# Ham-Dip-V2-004-A.net
KiCad netlist of a schematic drawn in EAGLE
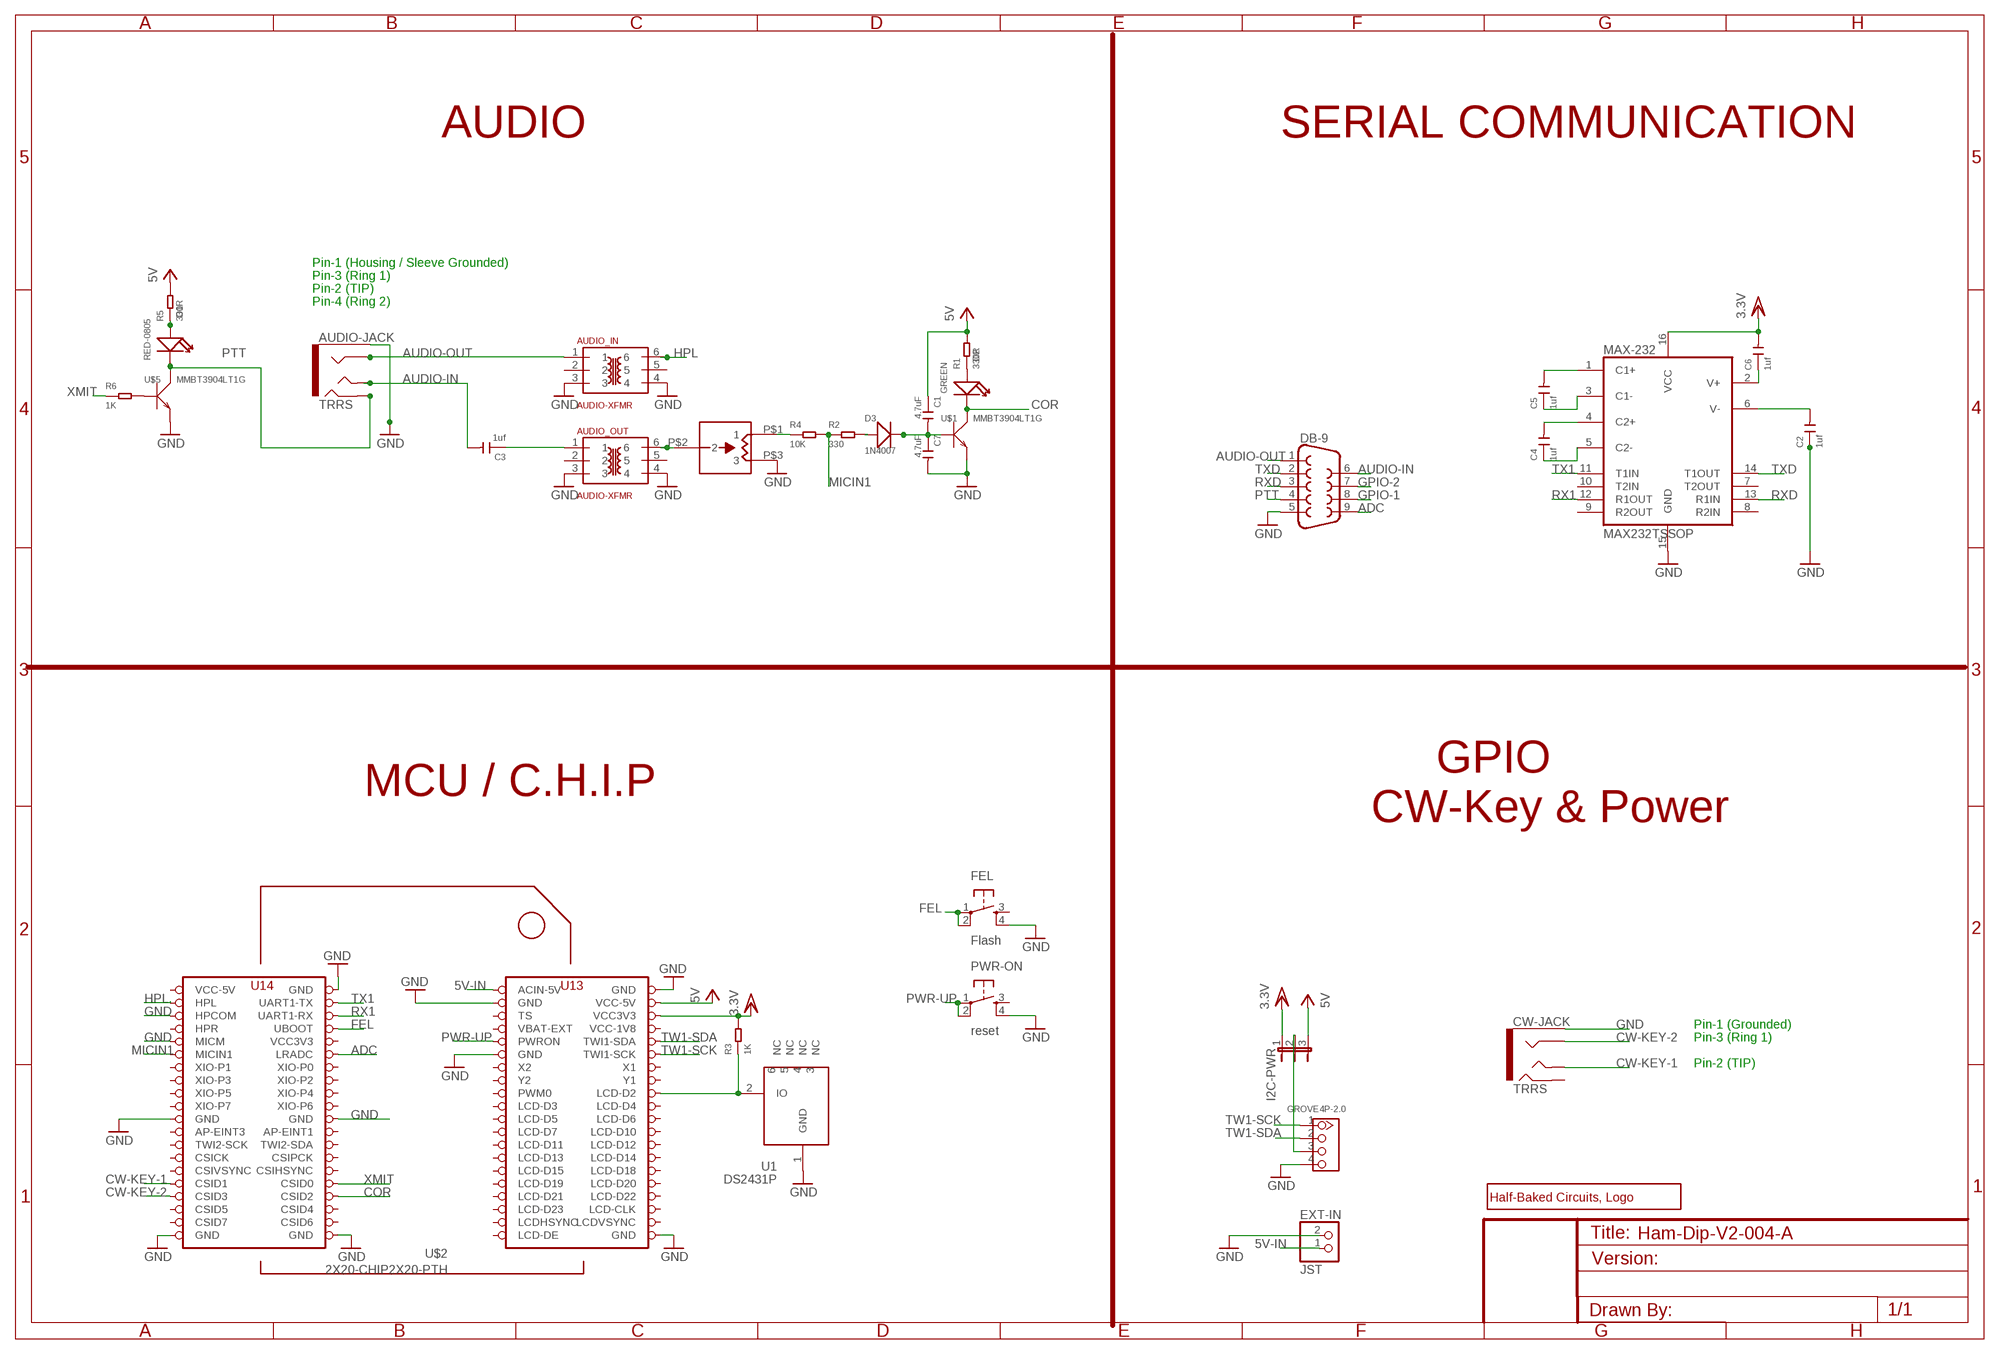
[diagram p0: schematic, sheet 1]

(export (version "E")
  (design (tool "Eeschema 10.0.6"))
  (components
    (comp (ref "AUDIO-JACK")
      (value "TRRS")
      (footprint "eagle-import:AUDIO-JACK-TRRS-SMD")
      (libsource (lib "eagle-import") (part "AUDIO-JACK3"))
    )
    (comp (ref "AUDIO_IN")
      (value "AUDIO-XFMR")
      (footprint "eagle-import:SM-LP-5001")
      (libsource (lib "eagle-import") (part "SM-LP-5001"))
    )
    (comp (ref "AUDIO_OUT")
      (value "AUDIO-XFMR")
      (footprint "eagle-import:SM-LP-5001")
      (libsource (lib "eagle-import") (part "SM-LP-5001"))
    )
    (comp (ref "C1")
      (value "4.7uF")
      (footprint "eagle-import:C0805")
      (fields (field (name "MPN") "CC0805KKX7R8BB105"))
      (libsource (lib "eagle-import") (part "CERAMIC-1UF-25V-10%-X7R(0805)"))
    )
    (comp (ref "C2")
      (value "1uf")
      (footprint "eagle-import:C0805")
      (fields (field (name "MPN") "CC0805KKX7R8BB105"))
      (libsource (lib "eagle-import") (part "CERAMIC-1UF-25V-10%-X7R(0805)"))
    )
    (comp (ref "C3")
      (value "1uf")
      (footprint "eagle-import:C0805")
      (fields (field (name "MPN") "CC0805KKX7R8BB105"))
      (libsource (lib "eagle-import") (part "CERAMIC-1UF-25V-10%-X7R(0805)"))
    )
    (comp (ref "C4")
      (value "1uf")
      (footprint "eagle-import:C0805")
      (fields (field (name "MPN") "CC0805KKX7R8BB105"))
      (libsource (lib "eagle-import") (part "CERAMIC-1UF-25V-10%-X7R(0805)"))
    )
    (comp (ref "C5")
      (value "1uf")
      (footprint "eagle-import:C0805")
      (fields (field (name "MPN") "CC0805KKX7R8BB105"))
      (libsource (lib "eagle-import") (part "CERAMIC-1UF-25V-10%-X7R(0805)"))
    )
    (comp (ref "C6")
      (value "1uf")
      (footprint "eagle-import:C0805")
      (fields (field (name "MPN") "CC0805KKX7R8BB105"))
      (libsource (lib "eagle-import") (part "CERAMIC-1UF-25V-10%-X7R(0805)"))
    )
    (comp (ref "C7")
      (value "4.7uF")
      (footprint "eagle-import:C0805")
      (fields (field (name "MPN") "CC0805KKX7R8BB105"))
      (libsource (lib "eagle-import") (part "CERAMIC-1UF-25V-10%-X7R(0805)"))
    )
    (comp (ref "CW-JACK")
      (value "TRRS")
      (footprint "eagle-import:AUDIO-JACK-TRRS-SMD")
      (libsource (lib "eagle-import") (part "AUDIO-JACK3"))
    )
    (comp (ref "D1")
      (value "RED-0805")
      (footprint "eagle-import:LED-0805")
      (fields (field (name "MPN") "17-215SURC/S530-A2/TR8"))
      (libsource (lib "eagle-import") (part "SMD-LED-CLEAR-RED(0805)"))
    )
    (comp (ref "D2")
      (value "GREEN")
      (footprint "eagle-import:LED-0805")
      (fields (field (name "MPN") "17-215SURC/S530-A2/TR8"))
      (libsource (lib "eagle-import") (part "SMD-LED-CLEAR-RED(0805)"))
    )
    (comp (ref "D3")
      (value "1N4007")
      (footprint "eagle-import:DO-214AC")
      (libsource (lib "eagle-import") (part "DIODE-GEN-PURPOSE-1KV-1A(DO-214AC)"))
    )
    (comp (ref "DB-9")
      (value "DB9FEMALE")
      (footprint "eagle-import:DB9")
      (libsource (lib "eagle-import") (part "DB9FEMALE"))
    )
    (comp (ref "EXT-IN")
      (value "JST")
      (footprint "eagle-import:JST-PH-2-THM")
      (libsource (lib "eagle-import") (part "JST_2PIN-THM"))
    )
    (comp (ref "FEL")
      (value "Flash")
      (footprint "eagle-import:TACTILE_SWITCH_SMD")
      (libsource (lib "eagle-import") (part "TAC_SWITCHSMD"))
    )
    (comp (ref "GROVE")
      (value "4P-2.0")
      (footprint "eagle-import:HW4-2.0")
      (libsource (lib "eagle-import") (part "GROVE-CONNECTOR-DIP(4P-2.0)"))
    )
    (comp (ref "I2C-PWR")
      (value "JP2E")
      (footprint "eagle-import:JP2")
      (libsource (lib "eagle-import") (part "JP2E"))
    )
    (comp (ref "MAX-232")
      (value "MAX232TSSOP")
      (footprint "eagle-import:TSSOP16")
      (libsource (lib "eagle-import") (part "MAX232TSSOP"))
    )
    (comp (ref "MIC-LVL")
      (value "1K")
      (footprint "eagle-import:TC33X")
      (libsource (lib "eagle-import") (part "TC33X"))
    )
    (comp (ref "PWR-ON")
      (value "reset")
      (footprint "eagle-import:TACTILE_SWITCH_SMD")
      (libsource (lib "eagle-import") (part "TAC_SWITCHSMD"))
    )
    (comp (ref "R1")
      (value "330R")
      (footprint "eagle-import:R0805")
      (fields (field (name "MPN") "RC0805JR-07220RL"))
      (libsource (lib "eagle-import") (part "SMD-RES-220R-5%-1/8W(0805)"))
    )
    (comp (ref "R2")
      (value "330")
      (footprint "eagle-import:R0805")
      (fields (field (name "MPN") "RC0805JR-07220RL"))
      (libsource (lib "eagle-import") (part "SMD-RES-220R-5%-1/8W(0805)"))
    )
    (comp (ref "R3")
      (value "1K")
      (footprint "eagle-import:R0805")
      (fields (field (name "MPN") "RC0805JR-07220RL"))
      (libsource (lib "eagle-import") (part "SMD-RES-220R-5%-1/8W(0805)"))
    )
    (comp (ref "R4")
      (value "10K")
      (footprint "eagle-import:R0805")
      (fields (field (name "MPN") "RC0805FR-0710KL"))
      (libsource (lib "eagle-import") (part "SMD-RES-10K-1%-1/8W(0805)"))
    )
    (comp (ref "R5")
      (value "330R")
      (footprint "eagle-import:R0805")
      (fields (field (name "MPN") "RC0805JR-07220RL"))
      (libsource (lib "eagle-import") (part "SMD-RES-220R-5%-1/8W(0805)"))
    )
    (comp (ref "R6")
      (value "1K")
      (footprint "eagle-import:R0805")
      (fields (field (name "MPN") "RC0805JR-07220RL"))
      (libsource (lib "eagle-import") (part "SMD-RES-220R-5%-1/8W(0805)"))
    )
    (comp (ref "U$1")
      (value "MMBT3904LT1G")
      (footprint "eagle-import:SOT-23")
      (libsource (lib "eagle-import") (part "SMD-TRANSISTORS-NPN-40V-200MA-MMBT3904LT1G(SOT-23)"))
    )
    (comp (ref "U$2")
      (value "2X20-CHIP2X20-PTH")
      (footprint "eagle-import:2X20CHIP-TH")
      (fields (field (name "VENDOR_PART_NUMBER") "AWHW40-G-SMD-R (single)"))
      (libsource (lib "eagle-import") (part "2X20-CHIP2X20-PTH-CHIP_A"))
    )
    (comp (ref "U$4")
      (value "HAM-DIP")
      (footprint "eagle-import:HAM-DIP")
      (libsource (lib "eagle-import") (part "HAM-DIP"))
    )
    (comp (ref "U$5")
      (value "MMBT3904LT1G")
      (footprint "eagle-import:SOT-23")
      (libsource (lib "eagle-import") (part "SMD-TRANSISTORS-NPN-40V-200MA-MMBT3904LT1G(SOT-23)"))
    )
    (comp (ref "U1")
      (value "DS2431P")
      (footprint "eagle-import:TSOC6")
      (fields (field (name "MFG") "DIGIKEY") (field (name "VENDOR_PART_NUMBER") "DS2431P+T&R"))
      (libsource (lib "eagle-import") (part "DS2431P"))
    )
  )
  (nets
    (net (code "1") (name "/5V-IN") (class "Default")
      (node (ref "EXT-IN") (pin "1") (pinfunction "2_1") (pintype "passive"))
      (node (ref "U$2") (pin "CHG-IN") (pinfunction "ACIN-5V_CHG-IN") (pintype "passive"))
    )
    (net (code "2") (name "/ADC") (class "Default")
      (node (ref "DB-9") (pin "9") (pinfunction "9_9") (pintype "passive"))
      (node (ref "U$2") (pin "LRADC") (pinfunction "LRADC_LRADC") (pintype "passive"))
    )
    (net (code "3") (name "/AUDIO-IN") (class "Default")
      (node (ref "AUDIO-JACK") (pin "TIP") (pinfunction "TIP_TIP") (pintype "bidirectional"))
      (node (ref "C3") (pin "2") (pinfunction "2_2") (pintype "passive"))
      (node (ref "DB-9") (pin "6") (pinfunction "6_6") (pintype "passive"))
    )
    (net (code "4") (name "/AUDIO-OUT") (class "Default")
      (node (ref "AUDIO-JACK") (pin "RING1") (pinfunction "RING1_RING1") (pintype "bidirectional"))
      (node (ref "AUDIO_IN") (pin "1") (pinfunction "1_1") (pintype "bidirectional"))
      (node (ref "DB-9") (pin "1") (pinfunction "1_1") (pintype "passive"))
    )
    (net (code "5") (name "/COR") (class "Default")
      (node (ref "D2") (pin "-") (pinfunction "-_-") (pintype "passive"))
      (node (ref "U$1") (pin "3") (pinfunction "C_3") (pintype "passive"))
      (node (ref "U$2") (pin "CSID2") (pinfunction "CSID2_CSID2") (pintype "passive"))
    )
    (net (code "6") (name "/CW-KEY-1") (class "Default")
      (node (ref "CW-JACK") (pin "TIP") (pinfunction "TIP_TIP") (pintype "bidirectional"))
      (node (ref "U$2") (pin "CSID1") (pinfunction "CSID1_CSID1") (pintype "passive"))
    )
    (net (code "7") (name "/CW-KEY-2") (class "Default")
      (node (ref "CW-JACK") (pin "RING1") (pinfunction "RING1_RING1") (pintype "bidirectional"))
      (node (ref "U$2") (pin "CSID3") (pinfunction "CSID3_CSID3") (pintype "passive"))
    )
    (net (code "8") (name "/FEL") (class "Default")
      (node (ref "FEL") (pin "1") (pinfunction "1_1") (pintype "passive"))
      (node (ref "FEL") (pin "2") (pinfunction "2_2") (pintype "passive"))
      (node (ref "U$2") (pin "FEL") (pinfunction "UBOOT_FEL") (pintype "passive"))
    )
    (net (code "9") (name "/GPIO-1") (class "Default")
      (node (ref "DB-9") (pin "8") (pinfunction "8_8") (pintype "passive"))
    )
    (net (code "10") (name "/GPIO-2") (class "Default")
      (node (ref "DB-9") (pin "7") (pinfunction "7_7") (pintype "passive"))
    )
    (net (code "11") (name "/HPL") (class "Default")
      (node (ref "AUDIO_IN") (pin "6") (pinfunction "6_6") (pintype "bidirectional"))
      (node (ref "U$2") (pin "HPL") (pinfunction "HPL_HPL") (pintype "passive"))
    )
    (net (code "12") (name "/MICIN1") (class "Default")
      (node (ref "R2") (pin "1") (pinfunction "1_1") (pintype "passive"))
      (node (ref "R4") (pin "2") (pinfunction "2_2") (pintype "passive"))
      (node (ref "U$2") (pin "MICIN1") (pinfunction "MICIN1_MICIN1") (pintype "passive"))
    )
    (net (code "13") (name "/PTT") (class "Default")
      (node (ref "AUDIO-JACK") (pin "RING2") (pinfunction "RING2_RING2") (pintype "bidirectional"))
      (node (ref "D1") (pin "-") (pinfunction "-_-") (pintype "passive"))
      (node (ref "DB-9") (pin "4") (pinfunction "4_4") (pintype "passive"))
      (node (ref "U$5") (pin "3") (pinfunction "C_3") (pintype "passive"))
    )
    (net (code "14") (name "/PWR-UP") (class "Default")
      (node (ref "PWR-ON") (pin "1") (pinfunction "1_1") (pintype "passive"))
      (node (ref "PWR-ON") (pin "2") (pinfunction "2_2") (pintype "passive"))
      (node (ref "U$2") (pin "PWRON") (pinfunction "PWRON_PWRON") (pintype "passive"))
    )
    (net (code "15") (name "/RX1") (class "Default")
      (node (ref "MAX-232") (pin "12") (pinfunction "R1OUT_12") (pintype "output"))
      (node (ref "U$2") (pin "UART1-RX") (pinfunction "UART1-RX_UART1-RX") (pintype "passive"))
    )
    (net (code "16") (name "/RXD") (class "Default")
      (node (ref "DB-9") (pin "3") (pinfunction "3_3") (pintype "passive"))
      (node (ref "MAX-232") (pin "13") (pinfunction "R1IN_13") (pintype "input"))
    )
    (net (code "17") (name "/TW1-SCK") (class "Default")
      (node (ref "GROVE") (pin "1") (pinfunction "1_1") (pintype "bidirectional"))
      (node (ref "U$2") (pin "TWI1-SCK") (pinfunction "TWI1-SCK_TWI1-SCK") (pintype "passive"))
    )
    (net (code "18") (name "/TW1-SDA") (class "Default")
      (node (ref "GROVE") (pin "2") (pinfunction "2_2") (pintype "bidirectional"))
      (node (ref "U$2") (pin "TWI1-SDA") (pinfunction "TWI1-SDA_TWI1-SDA") (pintype "passive"))
    )
    (net (code "19") (name "/TX1") (class "Default")
      (node (ref "MAX-232") (pin "11") (pinfunction "T1IN_11") (pintype "input"))
      (node (ref "U$2") (pin "UART1-TX") (pinfunction "UART1-TX_UART1-TX") (pintype "passive"))
    )
    (net (code "20") (name "/TXD") (class "Default")
      (node (ref "DB-9") (pin "2") (pinfunction "2_2") (pintype "passive"))
      (node (ref "MAX-232") (pin "14") (pinfunction "T1OUT_14") (pintype "output"))
    )
    (net (code "21") (name "/VCC-1V8") (class "Default")
      (node (ref "U$2") (pin "VCC1V8") (pinfunction "VCC-1V8_VCC1V8") (pintype "power_in"))
    )
    (net (code "22") (name "/VCC-5V") (class "Default")
      (node (ref "U$2") (pin "VCC5V@1") (pinfunction "VCC-5V_VCC5V@1") (pintype "power_in"))
    )
    (net (code "23") (name "/VCC3V3") (class "Default")
      (node (ref "U$2") (pin "VCC3V3@1") (pinfunction "VCC3V3_VCC3V3@1") (pintype "power_in"))
    )
    (net (code "24") (name "/XMIT") (class "Default")
      (node (ref "R6") (pin "1") (pinfunction "1_1") (pintype "passive"))
      (node (ref "U$2") (pin "CSID0") (pinfunction "CSID0_CSID0") (pintype "passive"))
    )
    (net (code "25") (name "3.3V") (class "Default")
      (node (ref "C6") (pin "2") (pinfunction "2_2") (pintype "passive"))
      (node (ref "I2C-PWR") (pin "1") (pinfunction "1_1") (pintype "passive"))
      (node (ref "MAX-232") (pin "16") (pinfunction "VCC_16") (pintype "bidirectional"))
      (node (ref "R3") (pin "2") (pinfunction "2_2") (pintype "passive"))
      (node (ref "U$2") (pin "VCC3V3") (pinfunction "VCC3V3_VCC3V3") (pintype "power_in"))
    )
    (net (code "26") (name "5V") (class "Default")
      (node (ref "C1") (pin "1") (pinfunction "1_1") (pintype "passive"))
      (node (ref "I2C-PWR") (pin "3") (pinfunction "3_3") (pintype "passive"))
      (node (ref "R1") (pin "2") (pinfunction "2_2") (pintype "passive"))
      (node (ref "R5") (pin "2") (pinfunction "2_2") (pintype "passive"))
      (node (ref "U$2") (pin "VCC5V@0") (pinfunction "VCC-5V_VCC5V@0") (pintype "power_in"))
    )
    (net (code "27") (name "GND") (class "Default")
      (node (ref "AUDIO-JACK") (pin "EARTH") (pinfunction "EARTH_EARTH") (pintype "bidirectional"))
      (node (ref "AUDIO_IN") (pin "3") (pinfunction "3_3") (pintype "bidirectional"))
      (node (ref "AUDIO_IN") (pin "4") (pinfunction "4_4") (pintype "bidirectional"))
      (node (ref "AUDIO_OUT") (pin "3") (pinfunction "3_3") (pintype "bidirectional"))
      (node (ref "AUDIO_OUT") (pin "4") (pinfunction "4_4") (pintype "bidirectional"))
      (node (ref "C2") (pin "1") (pinfunction "1_1") (pintype "passive"))
      (node (ref "C7") (pin "2") (pinfunction "2_2") (pintype "passive"))
      (node (ref "CW-JACK") (pin "EARTH") (pinfunction "EARTH_EARTH") (pintype "bidirectional"))
      (node (ref "DB-9") (pin "5") (pinfunction "5_5") (pintype "passive"))
      (node (ref "EXT-IN") (pin "2") (pinfunction "1_2") (pintype "passive"))
      (node (ref "FEL") (pin "4") (pinfunction "4_4") (pintype "passive"))
      (node (ref "GROVE") (pin "4") (pinfunction "4_4") (pintype "bidirectional"))
      (node (ref "MAX-232") (pin "15") (pinfunction "GND_15") (pintype "bidirectional"))
      (node (ref "MIC-LVL") (pin "P$3") (pinfunction "3_P$3") (pintype "bidirectional"))
      (node (ref "PWR-ON") (pin "4") (pinfunction "4_4") (pintype "passive"))
      (node (ref "U$1") (pin "2") (pinfunction "E_2") (pintype "passive"))
      (node (ref "U$2") (pin "GND@1") (pinfunction "GND_GND@1") (pintype "power_in"))
      (node (ref "U$2") (pin "GND@10") (pinfunction "GND_GND@10") (pintype "power_in"))
      (node (ref "U$2") (pin "GND@2") (pinfunction "GND_GND@2") (pintype "power_in"))
      (node (ref "U$2") (pin "GND@3") (pinfunction "GND_GND@3") (pintype "power_in"))
      (node (ref "U$2") (pin "GND@4") (pinfunction "GND_GND@4") (pintype "power_in"))
      (node (ref "U$2") (pin "GND@5") (pinfunction "GND_GND@5") (pintype "power_in"))
      (node (ref "U$2") (pin "GND@6") (pinfunction "GND_GND@6") (pintype "power_in"))
      (node (ref "U$2") (pin "GND@7") (pinfunction "GND_GND@7") (pintype "power_in"))
      (node (ref "U$2") (pin "GND@8") (pinfunction "GND_GND@8") (pintype "power_in"))
      (node (ref "U$2") (pin "HPCOM") (pinfunction "HPCOM_HPCOM") (pintype "passive"))
      (node (ref "U$2") (pin "MICM") (pinfunction "MICM_MICM") (pintype "passive"))
      (node (ref "U$5") (pin "2") (pinfunction "E_2") (pintype "passive"))
      (node (ref "U1") (pin "1") (pinfunction "GND_1") (pintype "bidirectional"))
    )
    (net (code "28") (name "Net-(AUDIO_OUT-Pad1)") (class "Default")
      (node (ref "AUDIO_OUT") (pin "1") (pinfunction "1_1") (pintype "bidirectional"))
      (node (ref "C3") (pin "1") (pinfunction "1_1") (pintype "passive"))
    )
    (net (code "29") (name "Net-(D1-Pad+)") (class "Default")
      (node (ref "D1") (pin "+") (pinfunction "+_+") (pintype "passive"))
      (node (ref "R5") (pin "1") (pinfunction "1_1") (pintype "passive"))
    )
    (net (code "30") (name "Net-(D2-Pad+)") (class "Default")
      (node (ref "D2") (pin "+") (pinfunction "+_+") (pintype "passive"))
      (node (ref "R1") (pin "1") (pinfunction "1_1") (pintype "passive"))
    )
    (net (code "31") (name "Net-(D3-+)") (class "Default")
      (node (ref "D3") (pin "1") (pinfunction "+_1") (pintype "passive"))
      (node (ref "R2") (pin "2") (pinfunction "2_2") (pintype "passive"))
    )
    (net (code "32") (name "Net-(D3--)") (class "Default")
      (node (ref "C1") (pin "2") (pinfunction "2_2") (pintype "passive"))
      (node (ref "C7") (pin "1") (pinfunction "1_1") (pintype "passive"))
      (node (ref "D3") (pin "2") (pinfunction "-_2") (pintype "passive"))
      (node (ref "U$1") (pin "1") (pinfunction "B_1") (pintype "passive"))
    )
    (net (code "33") (name "Net-(GROVE-Pad3)") (class "Default")
      (node (ref "GROVE") (pin "3") (pinfunction "3_3") (pintype "bidirectional"))
      (node (ref "I2C-PWR") (pin "2") (pinfunction "2_2") (pintype "passive"))
    )
    (net (code "34") (name "Net-(MAX-232-C1+)") (class "Default")
      (node (ref "C5") (pin "2") (pinfunction "2_2") (pintype "passive"))
      (node (ref "MAX-232") (pin "1") (pinfunction "C1+_1") (pintype "bidirectional"))
    )
    (net (code "35") (name "Net-(MAX-232-C1-)") (class "Default")
      (node (ref "C5") (pin "1") (pinfunction "1_1") (pintype "passive"))
      (node (ref "MAX-232") (pin "3") (pinfunction "C1-_3") (pintype "bidirectional"))
    )
    (net (code "36") (name "Net-(MAX-232-C2+)") (class "Default")
      (node (ref "C4") (pin "2") (pinfunction "2_2") (pintype "passive"))
      (node (ref "MAX-232") (pin "4") (pinfunction "C2+_4") (pintype "bidirectional"))
    )
    (net (code "37") (name "Net-(MAX-232-C2-)") (class "Default")
      (node (ref "C4") (pin "1") (pinfunction "1_1") (pintype "passive"))
      (node (ref "MAX-232") (pin "5") (pinfunction "C2-_5") (pintype "bidirectional"))
    )
    (net (code "38") (name "Net-(MAX-232-V+)") (class "Default")
      (node (ref "C6") (pin "1") (pinfunction "1_1") (pintype "passive"))
      (node (ref "MAX-232") (pin "2") (pinfunction "V+_2") (pintype "bidirectional"))
    )
    (net (code "39") (name "Net-(MAX-232-V-)") (class "Default")
      (node (ref "C2") (pin "2") (pinfunction "2_2") (pintype "passive"))
      (node (ref "MAX-232") (pin "6") (pinfunction "V-_6") (pintype "bidirectional"))
    )
    (net (code "40") (name "Net-(MIC-LVL-1)") (class "Default")
      (node (ref "MIC-LVL") (pin "P$1") (pinfunction "1_P$1") (pintype "bidirectional"))
      (node (ref "R4") (pin "1") (pinfunction "1_1") (pintype "passive"))
    )
    (net (code "41") (name "Net-(MIC-LVL-2)") (class "Default")
      (node (ref "AUDIO_OUT") (pin "6") (pinfunction "6_6") (pintype "bidirectional"))
      (node (ref "MIC-LVL") (pin "P$2") (pinfunction "2_P$2") (pintype "bidirectional"))
    )
    (net (code "42") (name "Net-(U$5-B)") (class "Default")
      (node (ref "R6") (pin "2") (pinfunction "2_2") (pintype "passive"))
      (node (ref "U$5") (pin "1") (pinfunction "B_1") (pintype "passive"))
    )
    (net (code "43") (name "Net-(U1-IO)") (class "Default")
      (node (ref "R3") (pin "1") (pinfunction "1_1") (pintype "passive"))
      (node (ref "U$2") (pin "LCD-D2") (pinfunction "LCD-D2_LCD-D2") (pintype "passive"))
      (node (ref "U1") (pin "2") (pinfunction "IO_2") (pintype "bidirectional"))
    )
    (net (code "44") (name "unconnected-(AUDIO_IN-Pad2)") (class "Default")
      (node (ref "AUDIO_IN") (pin "2") (pinfunction "2_2") (pintype "bidirectional"))
    )
    (net (code "45") (name "unconnected-(AUDIO_IN-Pad5)") (class "Default")
      (node (ref "AUDIO_IN") (pin "5") (pinfunction "5_5") (pintype "bidirectional"))
    )
    (net (code "46") (name "unconnected-(AUDIO_OUT-Pad2)") (class "Default")
      (node (ref "AUDIO_OUT") (pin "2") (pinfunction "2_2") (pintype "bidirectional"))
    )
    (net (code "47") (name "unconnected-(AUDIO_OUT-Pad5)") (class "Default")
      (node (ref "AUDIO_OUT") (pin "5") (pinfunction "5_5") (pintype "bidirectional"))
    )
    (net (code "48") (name "unconnected-(CW-JACK-PadRING2)") (class "Default")
      (node (ref "CW-JACK") (pin "RING2") (pinfunction "RING2_RING2") (pintype "bidirectional"))
    )
    (net (code "49") (name "unconnected-(FEL-Pad3)") (class "Default")
      (node (ref "FEL") (pin "3") (pinfunction "3_3") (pintype "passive"))
    )
    (net (code "50") (name "unconnected-(MAX-232-R2IN-Pad8)") (class "Default")
      (node (ref "MAX-232") (pin "8") (pinfunction "R2IN_8") (pintype "input"))
    )
    (net (code "51") (name "unconnected-(MAX-232-R2OUT-Pad9)") (class "Default")
      (node (ref "MAX-232") (pin "9") (pinfunction "R2OUT_9") (pintype "output"))
    )
    (net (code "52") (name "unconnected-(MAX-232-T2IN-Pad10)") (class "Default")
      (node (ref "MAX-232") (pin "10") (pinfunction "T2IN_10") (pintype "input"))
    )
    (net (code "53") (name "unconnected-(MAX-232-T2OUT-Pad7)") (class "Default")
      (node (ref "MAX-232") (pin "7") (pinfunction "T2OUT_7") (pintype "output"))
    )
    (net (code "54") (name "unconnected-(PWR-ON-Pad3)") (class "Default")
      (node (ref "PWR-ON") (pin "3") (pinfunction "3_3") (pintype "passive"))
    )
    (net (code "55") (name "unconnected-(U$2-LCDHSYNC-PadLCD-HSYNC)") (class "Default")
      (node (ref "U$2") (pin "LCD-HSYNC") (pinfunction "LCDHSYNC_LCD-HSYNC") (pintype "passive"))
    )
    (net (code "56") (name "unconnected-(U$2-LCDVSYNC-PadLCD-VSYNC)") (class "Default")
      (node (ref "U$2") (pin "LCD-VSYNC") (pinfunction "LCDVSYNC_LCD-VSYNC") (pintype "passive"))
    )
    (net (code "57") (name "unconnected-(U$2-PadAP-EINT1)") (class "Default")
      (node (ref "U$2") (pin "AP-EINT1") (pinfunction "AP-EINT1_AP-EINT1") (pintype "passive"))
    )
    (net (code "58") (name "unconnected-(U$2-PadAP-EINT3)") (class "Default")
      (node (ref "U$2") (pin "AP-EINT3") (pinfunction "AP-EINT3_AP-EINT3") (pintype "passive"))
    )
    (net (code "59") (name "unconnected-(U$2-PadCSICK)") (class "Default")
      (node (ref "U$2") (pin "CSICK") (pinfunction "CSICK_CSICK") (pintype "passive"))
    )
    (net (code "60") (name "unconnected-(U$2-PadCSID4)") (class "Default")
      (node (ref "U$2") (pin "CSID4") (pinfunction "CSID4_CSID4") (pintype "passive"))
    )
    (net (code "61") (name "unconnected-(U$2-PadCSID5)") (class "Default")
      (node (ref "U$2") (pin "CSID5") (pinfunction "CSID5_CSID5") (pintype "passive"))
    )
    (net (code "62") (name "unconnected-(U$2-PadCSID6)") (class "Default")
      (node (ref "U$2") (pin "CSID6") (pinfunction "CSID6_CSID6") (pintype "passive"))
    )
    (net (code "63") (name "unconnected-(U$2-PadCSID7)") (class "Default")
      (node (ref "U$2") (pin "CSID7") (pinfunction "CSID7_CSID7") (pintype "passive"))
    )
    (net (code "64") (name "unconnected-(U$2-PadCSIHSYNC)") (class "Default")
      (node (ref "U$2") (pin "CSIHSYNC") (pinfunction "CSIHSYNC_CSIHSYNC") (pintype "passive"))
    )
    (net (code "65") (name "unconnected-(U$2-PadCSIPCK)") (class "Default")
      (node (ref "U$2") (pin "CSIPCK") (pinfunction "CSIPCK_CSIPCK") (pintype "passive"))
    )
    (net (code "66") (name "unconnected-(U$2-PadCSIVSYNC)") (class "Default")
      (node (ref "U$2") (pin "CSIVSYNC") (pinfunction "CSIVSYNC_CSIVSYNC") (pintype "passive"))
    )
    (net (code "67") (name "unconnected-(U$2-PadHPR)") (class "Default")
      (node (ref "U$2") (pin "HPR") (pinfunction "HPR_HPR") (pintype "passive"))
    )
    (net (code "68") (name "unconnected-(U$2-PadLCD-CLK)") (class "Default")
      (node (ref "U$2") (pin "LCD-CLK") (pinfunction "LCD-CLK_LCD-CLK") (pintype "passive"))
    )
    (net (code "69") (name "unconnected-(U$2-PadLCD-D3)") (class "Default")
      (node (ref "U$2") (pin "LCD-D3") (pinfunction "LCD-D3_LCD-D3") (pintype "passive"))
    )
    (net (code "70") (name "unconnected-(U$2-PadLCD-D4)") (class "Default")
      (node (ref "U$2") (pin "LCD-D4") (pinfunction "LCD-D4_LCD-D4") (pintype "passive"))
    )
    (net (code "71") (name "unconnected-(U$2-PadLCD-D5)") (class "Default")
      (node (ref "U$2") (pin "LCD-D5") (pinfunction "LCD-D5_LCD-D5") (pintype "passive"))
    )
    (net (code "72") (name "unconnected-(U$2-PadLCD-D6)") (class "Default")
      (node (ref "U$2") (pin "LCD-D6") (pinfunction "LCD-D6_LCD-D6") (pintype "passive"))
    )
    (net (code "73") (name "unconnected-(U$2-PadLCD-D7)") (class "Default")
      (node (ref "U$2") (pin "LCD-D7") (pinfunction "LCD-D7_LCD-D7") (pintype "passive"))
    )
    (net (code "74") (name "unconnected-(U$2-PadLCD-D10)") (class "Default")
      (node (ref "U$2") (pin "LCD-D10") (pinfunction "LCD-D10_LCD-D10") (pintype "passive"))
    )
    (net (code "75") (name "unconnected-(U$2-PadLCD-D11)") (class "Default")
      (node (ref "U$2") (pin "LCD-D11") (pinfunction "LCD-D11_LCD-D11") (pintype "passive"))
    )
    (net (code "76") (name "unconnected-(U$2-PadLCD-D12)") (class "Default")
      (node (ref "U$2") (pin "LCD-D12") (pinfunction "LCD-D12_LCD-D12") (pintype "passive"))
    )
    (net (code "77") (name "unconnected-(U$2-PadLCD-D13)") (class "Default")
      (node (ref "U$2") (pin "LCD-D13") (pinfunction "LCD-D13_LCD-D13") (pintype "passive"))
    )
    (net (code "78") (name "unconnected-(U$2-PadLCD-D14)") (class "Default")
      (node (ref "U$2") (pin "LCD-D14") (pinfunction "LCD-D14_LCD-D14") (pintype "passive"))
    )
    (net (code "79") (name "unconnected-(U$2-PadLCD-D15)") (class "Default")
      (node (ref "U$2") (pin "LCD-D15") (pinfunction "LCD-D15_LCD-D15") (pintype "passive"))
    )
    (net (code "80") (name "unconnected-(U$2-PadLCD-D18)") (class "Default")
      (node (ref "U$2") (pin "LCD-D18") (pinfunction "LCD-D18_LCD-D18") (pintype "passive"))
    )
    (net (code "81") (name "unconnected-(U$2-PadLCD-D19)") (class "Default")
      (node (ref "U$2") (pin "LCD-D19") (pinfunction "LCD-D19_LCD-D19") (pintype "passive"))
    )
    (net (code "82") (name "unconnected-(U$2-PadLCD-D20)") (class "Default")
      (node (ref "U$2") (pin "LCD-D20") (pinfunction "LCD-D20_LCD-D20") (pintype "passive"))
    )
    (net (code "83") (name "unconnected-(U$2-PadLCD-D21)") (class "Default")
      (node (ref "U$2") (pin "LCD-D21") (pinfunction "LCD-D21_LCD-D21") (pintype "passive"))
    )
    (net (code "84") (name "unconnected-(U$2-PadLCD-D22)") (class "Default")
      (node (ref "U$2") (pin "LCD-D22") (pinfunction "LCD-D22_LCD-D22") (pintype "passive"))
    )
    (net (code "85") (name "unconnected-(U$2-PadLCD-D23)") (class "Default")
      (node (ref "U$2") (pin "LCD-D23") (pinfunction "LCD-D23_LCD-D23") (pintype "passive"))
    )
    (net (code "86") (name "unconnected-(U$2-PadLCD-DE)") (class "Default")
      (node (ref "U$2") (pin "LCD-DE") (pinfunction "LCD-DE_LCD-DE") (pintype "passive"))
    )
    (net (code "87") (name "unconnected-(U$2-PadPWM0)") (class "Default")
      (node (ref "U$2") (pin "PWM0") (pinfunction "PWM0_PWM0") (pintype "passive"))
    )
    (net (code "88") (name "unconnected-(U$2-PadTS)") (class "Default")
      (node (ref "U$2") (pin "TS") (pinfunction "TS_TS") (pintype "passive"))
    )
    (net (code "89") (name "unconnected-(U$2-PadTWI2-SCK)") (class "Default")
      (node (ref "U$2") (pin "TWI2-SCK") (pinfunction "TWI2-SCK_TWI2-SCK") (pintype "passive"))
    )
    (net (code "90") (name "unconnected-(U$2-PadTWI2-SDA)") (class "Default")
      (node (ref "U$2") (pin "TWI2-SDA") (pinfunction "TWI2-SDA_TWI2-SDA") (pintype "passive"))
    )
    (net (code "91") (name "unconnected-(U$2-PadX1)") (class "Default")
      (node (ref "U$2") (pin "X1") (pinfunction "X1_X1") (pintype "passive"))
    )
    (net (code "92") (name "unconnected-(U$2-PadX2)") (class "Default")
      (node (ref "U$2") (pin "X2") (pinfunction "X2_X2") (pintype "passive"))
    )
    (net (code "93") (name "unconnected-(U$2-PadXIO-P0)") (class "Default")
      (node (ref "U$2") (pin "XIO-P0") (pinfunction "XIO-P0_XIO-P0") (pintype "passive"))
    )
    (net (code "94") (name "unconnected-(U$2-PadXIO-P1)") (class "Default")
      (node (ref "U$2") (pin "XIO-P1") (pinfunction "XIO-P1_XIO-P1") (pintype "passive"))
    )
    (net (code "95") (name "unconnected-(U$2-PadXIO-P2)") (class "Default")
      (node (ref "U$2") (pin "XIO-P2") (pinfunction "XIO-P2_XIO-P2") (pintype "passive"))
    )
    (net (code "96") (name "unconnected-(U$2-PadXIO-P3)") (class "Default")
      (node (ref "U$2") (pin "XIO-P3") (pinfunction "XIO-P3_XIO-P3") (pintype "passive"))
    )
    (net (code "97") (name "unconnected-(U$2-PadXIO-P4)") (class "Default")
      (node (ref "U$2") (pin "XIO-P4") (pinfunction "XIO-P4_XIO-P4") (pintype "passive"))
    )
    (net (code "98") (name "unconnected-(U$2-PadXIO-P5)") (class "Default")
      (node (ref "U$2") (pin "XIO-P5") (pinfunction "XIO-P5_XIO-P5") (pintype "passive"))
    )
    (net (code "99") (name "unconnected-(U$2-PadXIO-P6)") (class "Default")
      (node (ref "U$2") (pin "XIO-P6") (pinfunction "XIO-P6_XIO-P6") (pintype "passive"))
    )
    (net (code "100") (name "unconnected-(U$2-PadXIO-P7)") (class "Default")
      (node (ref "U$2") (pin "XIO-P7") (pinfunction "XIO-P7_XIO-P7") (pintype "passive"))
    )
    (net (code "101") (name "unconnected-(U$2-PadY1)") (class "Default")
      (node (ref "U$2") (pin "Y1") (pinfunction "Y1_Y1") (pintype "passive"))
    )
    (net (code "102") (name "unconnected-(U$2-PadY2)") (class "Default")
      (node (ref "U$2") (pin "Y2") (pinfunction "Y2_Y2") (pintype "passive"))
    )
    (net (code "103") (name "unconnected-(U$2-VBAT-EXT-PadBAT)") (class "Default")
      (node (ref "U$2") (pin "BAT") (pinfunction "VBAT-EXT_BAT") (pintype "passive"))
    )
    (net (code "104") (name "unconnected-(U1-NC-Pad3)") (class "Default")
      (node (ref "U1") (pin "3") (pinfunction "NC_3") (pintype "bidirectional"))
    )
    (net (code "105") (name "unconnected-(U1-NC-Pad4)") (class "Default")
      (node (ref "U1") (pin "4") (pinfunction "NC_4") (pintype "bidirectional"))
    )
    (net (code "106") (name "unconnected-(U1-NC-Pad5)") (class "Default")
      (node (ref "U1") (pin "5") (pinfunction "NC_5") (pintype "bidirectional"))
    )
    (net (code "107") (name "unconnected-(U1-NC-Pad6)") (class "Default")
      (node (ref "U1") (pin "6") (pinfunction "NC_6") (pintype "bidirectional"))
    )
  )
)
